# featherSynth.net
KiCad netlist of a schematic drawn in EAGLE
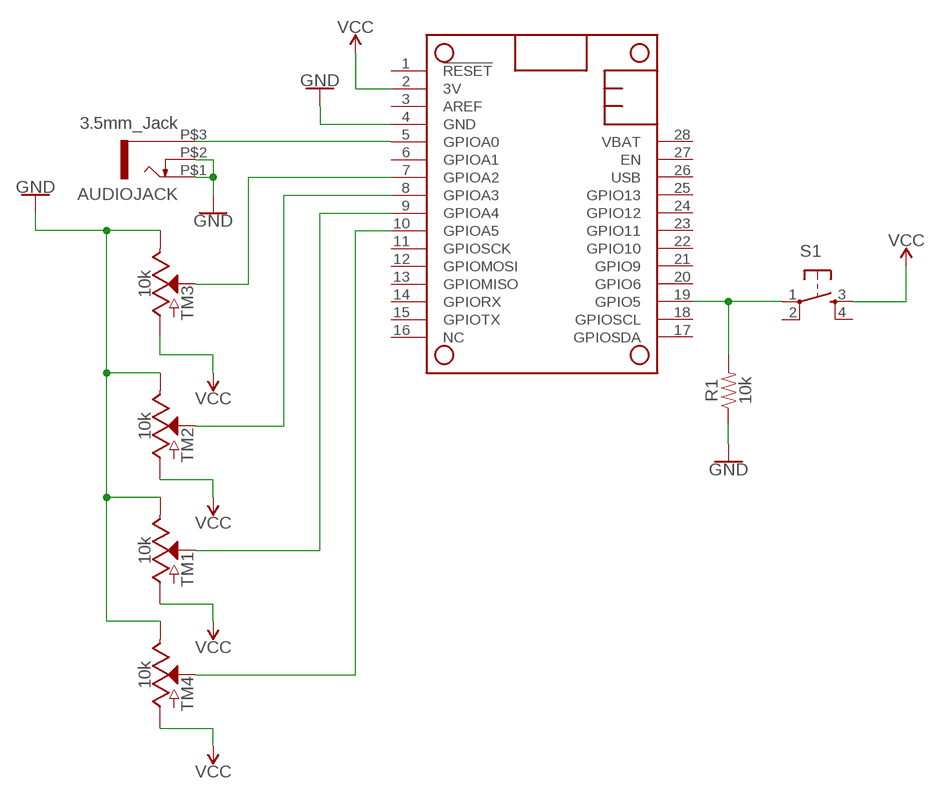
[diagram p0: schematic, sheet 1]

(export (version "E")
  (design (tool "Eeschema 10.0.6"))
  (components
    (comp (ref "AUDIOJACK")
      (value "3.5mm_Jack")
      (footprint "eagle-import:WQP-PJ301M-12_JACK")
      (libsource (lib "eagle-import") (part "WQP-PJ301M-12_JACK"))
    )
    (comp (ref "MS1")
      (value "FEATHERWING")
      (footprint "eagle-import:FEATHERWING")
      (libsource (lib "eagle-import") (part "FEATHERWING"))
    )
    (comp (ref "R1")
      (value "10k")
      (footprint "eagle-import:AXIAL-0.3")
      (libsource (lib "eagle-import") (part "1KOHM-HORIZ-1/4W-5%"))
    )
    (comp (ref "S1")
      (value "TAC_SWITCHPTH")
      (footprint "eagle-import:TACTILE-PTH")
      (libsource (lib "eagle-import") (part "TAC_SWITCHPTH"))
    )
    (comp (ref "TM1")
      (value "10k")
      (footprint "eagle-import:POT-PTH-ALPS")
      (libsource (lib "eagle-import") (part "POTENTIOMETER-PTH-9MM-1/20W-20%"))
    )
    (comp (ref "TM2")
      (value "10k")
      (footprint "eagle-import:POT-PTH-ALPS")
      (libsource (lib "eagle-import") (part "POTENTIOMETER-PTH-9MM-1/20W-20%"))
    )
    (comp (ref "TM3")
      (value "10k")
      (footprint "eagle-import:POT-PTH-ALPS")
      (libsource (lib "eagle-import") (part "POTENTIOMETER-PTH-9MM-1/20W-20%"))
    )
    (comp (ref "TM4")
      (value "10k")
      (footprint "eagle-import:POT-PTH-ALPS")
      (libsource (lib "eagle-import") (part "POTENTIOMETER-PTH-9MM-1/20W-20%"))
    )
  )
  (nets
    (net (code "1") (name "/USB") (class "Default")
      (node (ref "MS1") (pin "26") (pinfunction "USB_26") (pintype "power_in"))
    )
    (net (code "2") (name "/VBAT") (class "Default")
      (node (ref "MS1") (pin "28") (pinfunction "VBAT_28") (pintype "power_in"))
    )
    (net (code "3") (name "GND") (class "Default")
      (node (ref "AUDIOJACK") (pin "P$1") (pinfunction "2_P$1") (pintype "passive"))
      (node (ref "AUDIOJACK") (pin "P$2") (pinfunction "3_P$2") (pintype "passive"))
      (node (ref "MS1") (pin "4") (pinfunction "GND_4") (pintype "power_in"))
      (node (ref "R1") (pin "P$1") (pinfunction "1_P$1") (pintype "passive"))
      (node (ref "TM1") (pin "P$1") (pinfunction "E_P$1") (pintype "passive"))
      (node (ref "TM2") (pin "P$1") (pinfunction "E_P$1") (pintype "passive"))
      (node (ref "TM3") (pin "P$1") (pinfunction "E_P$1") (pintype "passive"))
      (node (ref "TM4") (pin "P$1") (pinfunction "E_P$1") (pintype "passive"))
    )
    (net (code "4") (name "Net-(AUDIOJACK-1)") (class "Default")
      (node (ref "AUDIOJACK") (pin "P$3") (pinfunction "1_P$3") (pintype "passive"))
      (node (ref "MS1") (pin "5") (pinfunction "GPIOA0_5") (pintype "bidirectional"))
    )
    (net (code "5") (name "Net-(MS1-GPIO5)") (class "Default")
      (node (ref "MS1") (pin "19") (pinfunction "GPIO5_19") (pintype "bidirectional"))
      (node (ref "R1") (pin "P$2") (pinfunction "2_P$2") (pintype "passive"))
      (node (ref "S1") (pin "1") (pinfunction "1_1") (pintype "passive"))
    )
    (net (code "6") (name "Net-(MS1-GPIOA2)") (class "Default")
      (node (ref "MS1") (pin "7") (pinfunction "GPIOA2_7") (pintype "bidirectional"))
      (node (ref "TM3") (pin "P$2") (pinfunction "S_P$2") (pintype "passive"))
    )
    (net (code "7") (name "Net-(MS1-GPIOA3)") (class "Default")
      (node (ref "MS1") (pin "8") (pinfunction "GPIOA3_8") (pintype "bidirectional"))
      (node (ref "TM2") (pin "P$2") (pinfunction "S_P$2") (pintype "passive"))
    )
    (net (code "8") (name "Net-(MS1-GPIOA4)") (class "Default")
      (node (ref "MS1") (pin "9") (pinfunction "GPIOA4_9") (pintype "bidirectional"))
      (node (ref "TM1") (pin "P$2") (pinfunction "S_P$2") (pintype "passive"))
    )
    (net (code "9") (name "Net-(MS1-GPIOA5)") (class "Default")
      (node (ref "MS1") (pin "10") (pinfunction "GPIOA5_10") (pintype "bidirectional"))
      (node (ref "TM4") (pin "P$2") (pinfunction "S_P$2") (pintype "passive"))
    )
    (net (code "10") (name "VCC") (class "Default")
      (node (ref "MS1") (pin "2") (pinfunction "3V_2") (pintype "power_in"))
      (node (ref "S1") (pin "3") (pinfunction "3_3") (pintype "passive"))
      (node (ref "TM1") (pin "P$3") (pinfunction "A_P$3") (pintype "passive"))
      (node (ref "TM2") (pin "P$3") (pinfunction "A_P$3") (pintype "passive"))
      (node (ref "TM3") (pin "P$3") (pinfunction "A_P$3") (pintype "passive"))
      (node (ref "TM4") (pin "P$3") (pinfunction "A_P$3") (pintype "passive"))
    )
    (net (code "11") (name "unconnected-(MS1-AREF-Pad3)") (class "Default")
      (node (ref "MS1") (pin "3") (pinfunction "AREF_3") (pintype "passive"))
    )
    (net (code "12") (name "unconnected-(MS1-EN-Pad27)") (class "Default")
      (node (ref "MS1") (pin "27") (pinfunction "EN_27") (pintype "passive"))
    )
    (net (code "13") (name "unconnected-(MS1-GPIO6-Pad20)") (class "Default")
      (node (ref "MS1") (pin "20") (pinfunction "GPIO6_20") (pintype "bidirectional"))
    )
    (net (code "14") (name "unconnected-(MS1-GPIO9-Pad21)") (class "Default")
      (node (ref "MS1") (pin "21") (pinfunction "GPIO9_21") (pintype "bidirectional"))
    )
    (net (code "15") (name "unconnected-(MS1-GPIO10-Pad22)") (class "Default")
      (node (ref "MS1") (pin "22") (pinfunction "GPIO10_22") (pintype "bidirectional"))
    )
    (net (code "16") (name "unconnected-(MS1-GPIO11-Pad23)") (class "Default")
      (node (ref "MS1") (pin "23") (pinfunction "GPIO11_23") (pintype "bidirectional"))
    )
    (net (code "17") (name "unconnected-(MS1-GPIO12-Pad24)") (class "Default")
      (node (ref "MS1") (pin "24") (pinfunction "GPIO12_24") (pintype "bidirectional"))
    )
    (net (code "18") (name "unconnected-(MS1-GPIO13-Pad25)") (class "Default")
      (node (ref "MS1") (pin "25") (pinfunction "GPIO13_25") (pintype "bidirectional"))
    )
    (net (code "19") (name "unconnected-(MS1-GPIOA1-Pad6)") (class "Default")
      (node (ref "MS1") (pin "6") (pinfunction "GPIOA1_6") (pintype "bidirectional"))
    )
    (net (code "20") (name "unconnected-(MS1-GPIOMISO-Pad13)") (class "Default")
      (node (ref "MS1") (pin "13") (pinfunction "GPIOMISO_13") (pintype "bidirectional"))
    )
    (net (code "21") (name "unconnected-(MS1-GPIOMOSI-Pad12)") (class "Default")
      (node (ref "MS1") (pin "12") (pinfunction "GPIOMOSI_12") (pintype "bidirectional"))
    )
    (net (code "22") (name "unconnected-(MS1-GPIORX-Pad14)") (class "Default")
      (node (ref "MS1") (pin "14") (pinfunction "GPIORX_14") (pintype "bidirectional"))
    )
    (net (code "23") (name "unconnected-(MS1-GPIOSCK-Pad11)") (class "Default")
      (node (ref "MS1") (pin "11") (pinfunction "GPIOSCK_11") (pintype "bidirectional"))
    )
    (net (code "24") (name "unconnected-(MS1-GPIOSCL-Pad18)") (class "Default")
      (node (ref "MS1") (pin "18") (pinfunction "GPIOSCL_18") (pintype "bidirectional"))
    )
    (net (code "25") (name "unconnected-(MS1-GPIOSDA-Pad17)") (class "Default")
      (node (ref "MS1") (pin "17") (pinfunction "GPIOSDA_17") (pintype "bidirectional"))
    )
    (net (code "26") (name "unconnected-(MS1-GPIOTX-Pad15)") (class "Default")
      (node (ref "MS1") (pin "15") (pinfunction "GPIOTX_15") (pintype "bidirectional"))
    )
    (net (code "27") (name "unconnected-(MS1-NC-Pad16)") (class "Default")
      (node (ref "MS1") (pin "16") (pinfunction "NC_16") (pintype "passive"))
    )
    (net (code "28") (name "unconnected-(MS1-~{RESET}-Pad1)") (class "Default")
      (node (ref "MS1") (pin "1") (pinfunction "~{RESET}_1") (pintype "input"))
    )
    (net (code "29") (name "unconnected-(S1-Pad2)") (class "Default")
      (node (ref "S1") (pin "2") (pinfunction "2_2") (pintype "passive"))
    )
    (net (code "30") (name "unconnected-(S1-Pad4)") (class "Default")
      (node (ref "S1") (pin "4") (pinfunction "4_4") (pintype "passive"))
    )
  )
)
